# mosquino.net
KiCad netlist of a schematic drawn in EAGLE
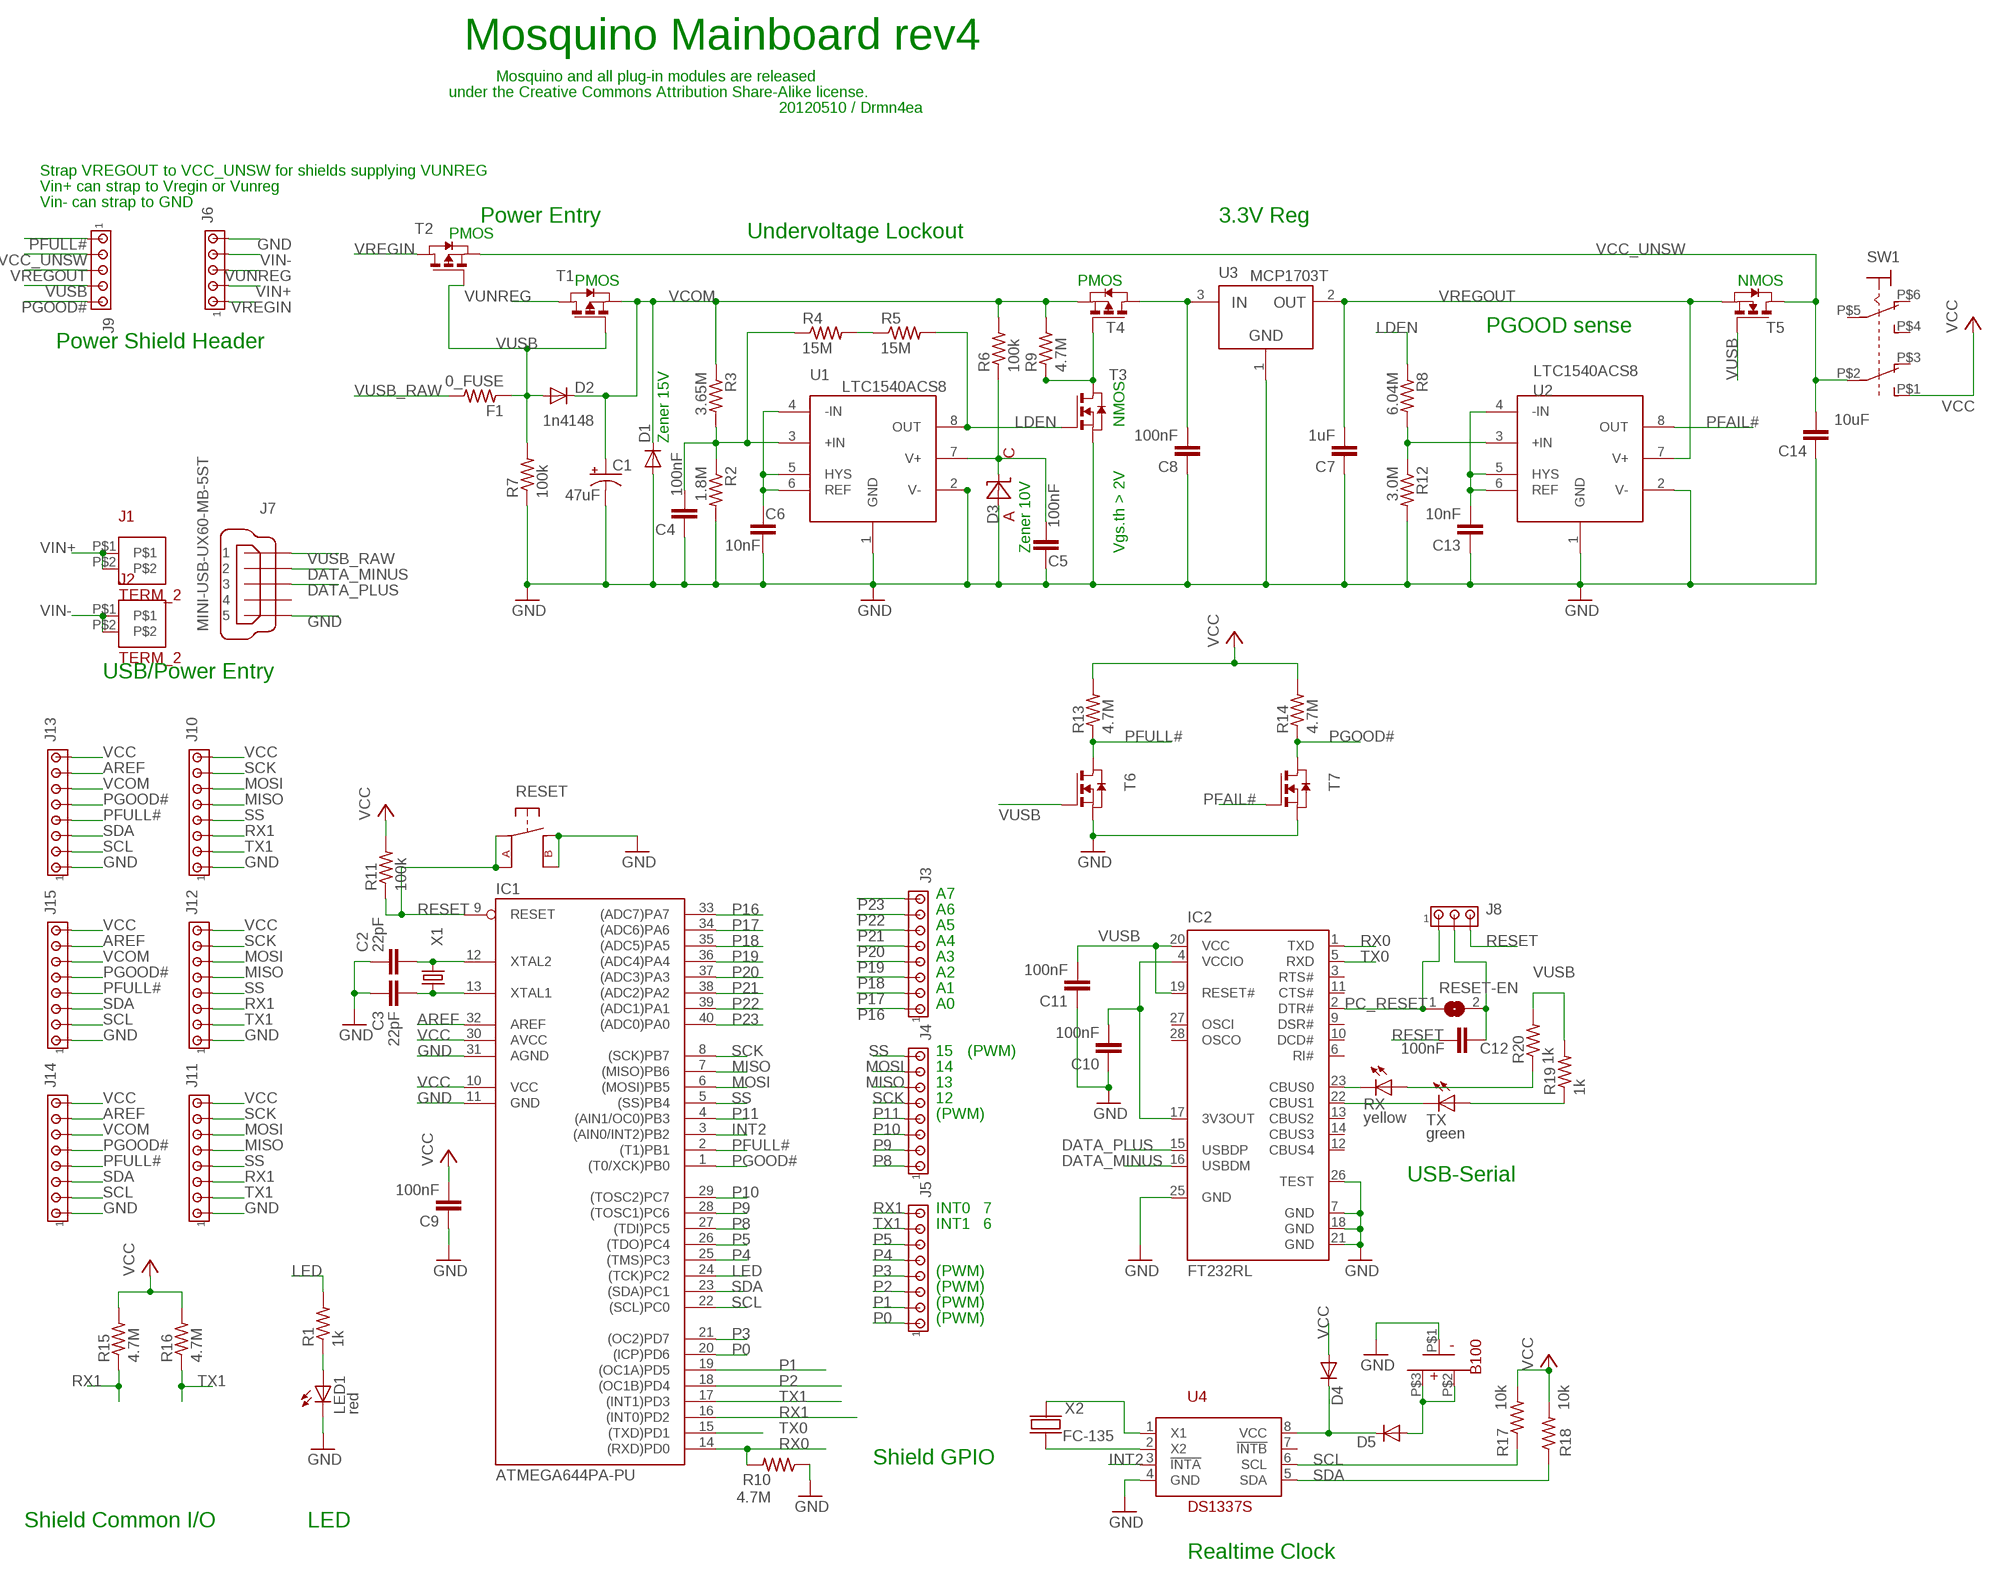
[diagram p0: schematic, sheet 1]

(export (version "E")
  (design (tool "Eeschema 10.0.6"))
  (components
    (comp (ref "B100")
      (value "BK885_CR1225_COIN_BATTERY_HOLDER_SMD")
      (footprint "eagle-import:BK885_CR1225_COIN_BATTERY_HOLDER_SMD")
      (libsource (lib "eagle-import") (part "BK885_CR1225_COIN_BATTERY_HOLDER_SMD"))
    )
    (comp (ref "C1")
      (value "47uF")
      (footprint "eagle-import:PANASONIC_D")
      (libsource (lib "eagle-import") (part "CPOL-USD"))
    )
    (comp (ref "C2")
      (value "22pF")
      (footprint "eagle-import:C0805K")
      (libsource (lib "eagle-import") (part "C-EUC0805K"))
    )
    (comp (ref "C3")
      (value "22pF")
      (footprint "eagle-import:C0805K")
      (libsource (lib "eagle-import") (part "C-EUC0805K"))
    )
    (comp (ref "C4")
      (value "100nF")
      (footprint "eagle-import:C0805")
      (libsource (lib "eagle-import") (part "C-EUC0805"))
    )
    (comp (ref "C5")
      (value "100nF")
      (footprint "eagle-import:C0805")
      (libsource (lib "eagle-import") (part "C-EUC0805"))
    )
    (comp (ref "C6")
      (value "10nF")
      (footprint "eagle-import:C0805")
      (libsource (lib "eagle-import") (part "C-EUC0805"))
    )
    (comp (ref "C7")
      (value "1uF")
      (footprint "eagle-import:C0805")
      (libsource (lib "eagle-import") (part "C-EUC0805"))
    )
    (comp (ref "C8")
      (value "100nF")
      (footprint "eagle-import:C0805")
      (libsource (lib "eagle-import") (part "C-EUC0805"))
    )
    (comp (ref "C9")
      (value "100nF")
      (footprint "eagle-import:C0805K")
      (libsource (lib "eagle-import") (part "C-EUC0805K"))
    )
    (comp (ref "C10")
      (value "100nF")
      (footprint "eagle-import:C0805K")
      (libsource (lib "eagle-import") (part "C-EUC0805K"))
    )
    (comp (ref "C11")
      (value "100nF")
      (footprint "eagle-import:C0805K")
      (libsource (lib "eagle-import") (part "C-EUC0805K"))
    )
    (comp (ref "C12")
      (value "100nF")
      (footprint "eagle-import:C0805K")
      (libsource (lib "eagle-import") (part "C-EUC0805K"))
    )
    (comp (ref "C13")
      (value "10nF")
      (footprint "eagle-import:C0805")
      (libsource (lib "eagle-import") (part "C-EUC0805"))
    )
    (comp (ref "C14")
      (value "10uF")
      (footprint "eagle-import:C0805K")
      (libsource (lib "eagle-import") (part "C-EUC0805K"))
    )
    (comp (ref "D1")
      (value "BZT52C15-7-F")
      (footprint "eagle-import:SOD123")
      (libsource (lib "eagle-import") (part "DIODE-SOD123"))
    )
    (comp (ref "D2")
      (value "1n4148")
      (footprint "eagle-import:SOD123")
      (libsource (lib "eagle-import") (part "DIODE-SOD123"))
    )
    (comp (ref "D3")
      (value "BZT52C10-7-F")
      (footprint "eagle-import:SOD123")
      (libsource (lib "eagle-import") (part "DIODE_ZENER_CZRM27C200P-G"))
    )
    (comp (ref "D4")
      (value "MMSD301T1G")
      (footprint "eagle-import:SOD123")
      (libsource (lib "eagle-import") (part "DIODE-SOD123"))
    )
    (comp (ref "D5")
      (value "MMSD301T1G")
      (footprint "eagle-import:SOD123")
      (libsource (lib "eagle-import") (part "DIODE-SOD123"))
    )
    (comp (ref "F1")
      (value "0_FUSE")
      (footprint "eagle-import:R0805")
      (libsource (lib "eagle-import") (part "R-US_R0805"))
    )
    (comp (ref "IC1")
      (value "ATMEGA644PA-PU")
      (footprint "eagle-import:DIL40")
      (libsource (lib "eagle-import") (part "MEGA323-P"))
    )
    (comp (ref "IC2")
      (value "FT232RL")
      (footprint "eagle-import:SSOP28")
      (libsource (lib "eagle-import") (part "FT232RL"))
    )
    (comp (ref "J1")
      (value "TERM_2")
      (footprint "eagle-import:TERM_3POINT5MM")
      (libsource (lib "eagle-import") (part "TERM_2"))
    )
    (comp (ref "J2")
      (value "TERM_2")
      (footprint "eagle-import:TERM_3POINT5MM")
      (libsource (lib "eagle-import") (part "TERM_2"))
    )
    (comp (ref "J3")
      (value "MTA08-100")
      (footprint "eagle-import:10X08MTA")
      (libsource (lib "eagle-import") (part "MTA08-100"))
    )
    (comp (ref "J4")
      (value "MTA08-100")
      (footprint "eagle-import:10X08MTA")
      (libsource (lib "eagle-import") (part "MTA08-100"))
    )
    (comp (ref "J5")
      (value "MTA08-100")
      (footprint "eagle-import:10X08MTA")
      (libsource (lib "eagle-import") (part "MTA08-100"))
    )
    (comp (ref "J6")
      (value "MTA05-100")
      (footprint "eagle-import:10X05MTA")
      (libsource (lib "eagle-import") (part "MTA05-100"))
    )
    (comp (ref "J7")
      (value "MINI-USB-UX60-MB-5ST")
      (footprint "eagle-import:UX60-MB-5ST")
      (libsource (lib "eagle-import") (part "MINI-USB-UX60-MB-5ST"))
    )
    (comp (ref "J8")
      (value "MTA03-100")
      (footprint "eagle-import:10X03MTA")
      (libsource (lib "eagle-import") (part "MTA03-100"))
    )
    (comp (ref "J9")
      (value "MTA05-100")
      (footprint "eagle-import:10X05MTA")
      (libsource (lib "eagle-import") (part "MTA05-100"))
    )
    (comp (ref "J10")
      (value "MTA08-100")
      (footprint "eagle-import:10X08MTA")
      (libsource (lib "eagle-import") (part "MTA08-100"))
    )
    (comp (ref "J11")
      (value "MTA08-100")
      (footprint "eagle-import:10X08MTA")
      (libsource (lib "eagle-import") (part "MTA08-100"))
    )
    (comp (ref "J12")
      (value "MTA08-100")
      (footprint "eagle-import:10X08MTA")
      (libsource (lib "eagle-import") (part "MTA08-100"))
    )
    (comp (ref "J13")
      (value "MTA08-100")
      (footprint "eagle-import:10X08MTA")
      (libsource (lib "eagle-import") (part "MTA08-100"))
    )
    (comp (ref "J14")
      (value "MTA08-100")
      (footprint "eagle-import:10X08MTA")
      (libsource (lib "eagle-import") (part "MTA08-100"))
    )
    (comp (ref "J15")
      (value "MTA08-100")
      (footprint "eagle-import:10X08MTA")
      (libsource (lib "eagle-import") (part "MTA08-100"))
    )
    (comp (ref "LED1")
      (value "red")
      (footprint "eagle-import:CHIP-LED0805")
      (libsource (lib "eagle-import") (part "LEDCHIP-LED0805"))
    )
    (comp (ref "R1")
      (value "1k")
      (footprint "eagle-import:R0805")
      (libsource (lib "eagle-import") (part "R-US_R0805"))
    )
    (comp (ref "R2")
      (value "1.8M")
      (footprint "eagle-import:R0805")
      (libsource (lib "eagle-import") (part "R-US_R0805"))
    )
    (comp (ref "R3")
      (value "3.65M")
      (footprint "eagle-import:R0805")
      (libsource (lib "eagle-import") (part "R-US_R0805"))
    )
    (comp (ref "R4")
      (value "15M")
      (footprint "eagle-import:R0805")
      (libsource (lib "eagle-import") (part "R-US_R0805"))
    )
    (comp (ref "R5")
      (value "15M")
      (footprint "eagle-import:R0805")
      (libsource (lib "eagle-import") (part "R-US_R0805"))
    )
    (comp (ref "R6")
      (value "100k")
      (footprint "eagle-import:R0805")
      (libsource (lib "eagle-import") (part "R-US_R0805"))
    )
    (comp (ref "R7")
      (value "100k")
      (footprint "eagle-import:R0805")
      (libsource (lib "eagle-import") (part "R-US_R0805"))
    )
    (comp (ref "R8")
      (value "6.04M")
      (footprint "eagle-import:R0805")
      (libsource (lib "eagle-import") (part "R-US_R0805"))
    )
    (comp (ref "R9")
      (value "4.7M")
      (footprint "eagle-import:R0805")
      (libsource (lib "eagle-import") (part "R-US_R0805"))
    )
    (comp (ref "R10")
      (value "4.7M")
      (footprint "eagle-import:R0805")
      (libsource (lib "eagle-import") (part "R-US_R0805"))
    )
    (comp (ref "R11")
      (value "100k")
      (footprint "eagle-import:R0805")
      (libsource (lib "eagle-import") (part "R-US_R0805"))
    )
    (comp (ref "R12")
      (value "3.0M")
      (footprint "eagle-import:R0805")
      (libsource (lib "eagle-import") (part "R-US_R0805"))
    )
    (comp (ref "R13")
      (value "4.7M")
      (footprint "eagle-import:R0805")
      (libsource (lib "eagle-import") (part "R-US_R0805"))
    )
    (comp (ref "R14")
      (value "4.7M")
      (footprint "eagle-import:R0805")
      (libsource (lib "eagle-import") (part "R-US_R0805"))
    )
    (comp (ref "R15")
      (value "4.7M")
      (footprint "eagle-import:R0805")
      (libsource (lib "eagle-import") (part "R-US_R0805"))
    )
    (comp (ref "R16")
      (value "4.7M")
      (footprint "eagle-import:R0805")
      (libsource (lib "eagle-import") (part "R-US_R0805"))
    )
    (comp (ref "R17")
      (value "10k")
      (footprint "eagle-import:R0805")
      (libsource (lib "eagle-import") (part "R-US_R0805"))
    )
    (comp (ref "R18")
      (value "10k")
      (footprint "eagle-import:R0805")
      (libsource (lib "eagle-import") (part "R-US_R0805"))
    )
    (comp (ref "R19")
      (value "1k")
      (footprint "eagle-import:R0805")
      (libsource (lib "eagle-import") (part "R-US_R0805"))
    )
    (comp (ref "R20")
      (value "1k")
      (footprint "eagle-import:R0805")
      (libsource (lib "eagle-import") (part "R-US_R0805"))
    )
    (comp (ref "RESET")
      (value "EVQ_TACT_SW_6X6POINT5")
      (footprint "eagle-import:EVQ_TACT_SW_6X6POINT5")
      (libsource (lib "eagle-import") (part "EVQ_TACT_SW_6X6POINT5"))
    )
    (comp (ref "RESET-EN")
      (value "SJ")
      (footprint "eagle-import:SJ")
      (libsource (lib "eagle-import") (part "SJ"))
    )
    (comp (ref "RX")
      (value "yellow")
      (footprint "eagle-import:CHIP-LED0805")
      (libsource (lib "eagle-import") (part "LEDCHIP-LED0805"))
    )
    (comp (ref "SW1")
      (value "SW_DPDT_EG1390")
      (footprint "eagle-import:EG1390_SWITCH_DPDT")
      (libsource (lib "eagle-import") (part "SW_DPDT_EG1390"))
    )
    (comp (ref "T1")
      (value "DMP3098L-7")
      (footprint "eagle-import:SOT-23")
      (libsource (lib "eagle-import") (part "PMOSSOT23"))
    )
    (comp (ref "T2")
      (value "DMP3098L-7")
      (footprint "eagle-import:SOT-23")
      (libsource (lib "eagle-import") (part "PMOSSOT23"))
    )
    (comp (ref "T3")
      (value "IRFML8244TRPBF")
      (footprint "eagle-import:SOT-23")
      (libsource (lib "eagle-import") (part "NMOSSOT23"))
    )
    (comp (ref "T4")
      (value "DMP3098L-7")
      (footprint "eagle-import:SOT-23")
      (libsource (lib "eagle-import") (part "PMOSSOT23"))
    )
    (comp (ref "T5")
      (value "BSH103")
      (footprint "eagle-import:SOT-23")
      (libsource (lib "eagle-import") (part "NMOSSOT23"))
    )
    (comp (ref "T6")
      (value "IRFML8244TRPBF")
      (footprint "eagle-import:SOT-23")
      (libsource (lib "eagle-import") (part "NMOSSOT23"))
    )
    (comp (ref "T7")
      (value "IRFML8244TRPBF")
      (footprint "eagle-import:SOT-23")
      (libsource (lib "eagle-import") (part "NMOSSOT23"))
    )
    (comp (ref "TX")
      (value "green")
      (footprint "eagle-import:CHIP-LED0805")
      (libsource (lib "eagle-import") (part "LEDCHIP-LED0805"))
    )
    (comp (ref "U1")
      (value "LTC1540ACS8")
      (footprint "eagle-import:SO-8")
      (libsource (lib "eagle-import") (part "LTC1540ACS8"))
    )
    (comp (ref "U2")
      (value "LTC1540ACS8")
      (footprint "eagle-import:SO-8")
      (libsource (lib "eagle-import") (part "LTC1540ACS8"))
    )
    (comp (ref "U3")
      (value "MCP1703T")
      (footprint "eagle-import:SOT23")
      (libsource (lib "eagle-import") (part "MCP1700T"))
    )
    (comp (ref "U4")
      (value "DS1337S")
      (footprint "eagle-import:SO-8")
      (libsource (lib "eagle-import") (part "DS1337S"))
    )
    (comp (ref "X1")
      (value "ABLS-4.000MHZ-B4-T")
      (footprint "eagle-import:SM49")
      (libsource (lib "eagle-import") (part "CRYSTALSM49"))
    )
    (comp (ref "X2")
      (value "FC-135")
      (footprint "eagle-import:FC-135")
      (libsource (lib "eagle-import") (part "FC-135"))
    )
  )
  (nets
    (net (code "1") (name "/AREF") (class "Default")
      (node (ref "IC1") (pin "32") (pinfunction "AREF_32") (pintype "power_in"))
      (node (ref "J13") (pin "7") (pinfunction "7_7") (pintype "passive"))
      (node (ref "J14") (pin "7") (pinfunction "7_7") (pintype "passive"))
      (node (ref "J15") (pin "7") (pinfunction "7_7") (pintype "passive"))
    )
    (net (code "2") (name "/DATA_MINUS") (class "Default")
      (node (ref "IC2") (pin "16") (pinfunction "USBDM_16") (pintype "input"))
      (node (ref "J7") (pin "2") (pinfunction "2_2") (pintype "input"))
    )
    (net (code "3") (name "/DATA_PLUS") (class "Default")
      (node (ref "IC2") (pin "15") (pinfunction "USBDP_15") (pintype "input"))
      (node (ref "J7") (pin "3") (pinfunction "3_3") (pintype "input"))
    )
    (net (code "4") (name "/INT2") (class "Default")
      (node (ref "IC1") (pin "3") (pinfunction "(AIN0/INT2)PB2_3") (pintype "bidirectional"))
      (node (ref "U4") (pin "3") (pinfunction "~{INTA}_3") (pintype "bidirectional"))
    )
    (net (code "5") (name "/LDEN") (class "Default")
      (node (ref "R5") (pin "2") (pinfunction "2_2") (pintype "passive"))
      (node (ref "R8") (pin "1") (pinfunction "1_1") (pintype "passive"))
      (node (ref "T3") (pin "3") (pinfunction "G_3") (pintype "passive"))
      (node (ref "U1") (pin "8") (pinfunction "OUT_8") (pintype "bidirectional"))
    )
    (net (code "6") (name "/LED") (class "Default")
      (node (ref "IC1") (pin "24") (pinfunction "(TCK)PC2_24") (pintype "bidirectional"))
      (node (ref "R1") (pin "2") (pinfunction "2_2") (pintype "passive"))
    )
    (net (code "7") (name "/MISO") (class "Default")
      (node (ref "IC1") (pin "7") (pinfunction "(MISO)PB6_7") (pintype "bidirectional"))
      (node (ref "J10") (pin "5") (pinfunction "5_5") (pintype "passive"))
      (node (ref "J11") (pin "5") (pinfunction "5_5") (pintype "passive"))
      (node (ref "J12") (pin "5") (pinfunction "5_5") (pintype "passive"))
      (node (ref "J4") (pin "6") (pinfunction "6_6") (pintype "passive"))
    )
    (net (code "8") (name "/MOSI") (class "Default")
      (node (ref "IC1") (pin "6") (pinfunction "(MOSI)PB5_6") (pintype "bidirectional"))
      (node (ref "J10") (pin "6") (pinfunction "6_6") (pintype "passive"))
      (node (ref "J11") (pin "6") (pinfunction "6_6") (pintype "passive"))
      (node (ref "J12") (pin "6") (pinfunction "6_6") (pintype "passive"))
      (node (ref "J4") (pin "7") (pinfunction "7_7") (pintype "passive"))
    )
    (net (code "9") (name "/P0") (class "Default")
      (node (ref "IC1") (pin "20") (pinfunction "(ICP)PD6_20") (pintype "bidirectional"))
      (node (ref "J5") (pin "1") (pinfunction "1_1") (pintype "passive"))
    )
    (net (code "10") (name "/P1") (class "Default")
      (node (ref "IC1") (pin "19") (pinfunction "(OC1A)PD5_19") (pintype "bidirectional"))
      (node (ref "J5") (pin "2") (pinfunction "2_2") (pintype "passive"))
    )
    (net (code "11") (name "/P2") (class "Default")
      (node (ref "IC1") (pin "18") (pinfunction "(OC1B)PD4_18") (pintype "bidirectional"))
      (node (ref "J5") (pin "3") (pinfunction "3_3") (pintype "passive"))
    )
    (net (code "12") (name "/P3") (class "Default")
      (node (ref "IC1") (pin "21") (pinfunction "(OC2)PD7_21") (pintype "bidirectional"))
      (node (ref "J5") (pin "4") (pinfunction "4_4") (pintype "passive"))
    )
    (net (code "13") (name "/P4") (class "Default")
      (node (ref "IC1") (pin "25") (pinfunction "(TMS)PC3_25") (pintype "bidirectional"))
      (node (ref "J5") (pin "5") (pinfunction "5_5") (pintype "passive"))
    )
    (net (code "14") (name "/P5") (class "Default")
      (node (ref "IC1") (pin "26") (pinfunction "(TDO)PC4_26") (pintype "bidirectional"))
      (node (ref "J5") (pin "6") (pinfunction "6_6") (pintype "passive"))
    )
    (net (code "15") (name "/P8") (class "Default")
      (node (ref "IC1") (pin "27") (pinfunction "(TDI)PC5_27") (pintype "bidirectional"))
      (node (ref "J4") (pin "1") (pinfunction "1_1") (pintype "passive"))
    )
    (net (code "16") (name "/P9") (class "Default")
      (node (ref "IC1") (pin "28") (pinfunction "(TOSC1)PC6_28") (pintype "bidirectional"))
      (node (ref "J4") (pin "2") (pinfunction "2_2") (pintype "passive"))
    )
    (net (code "17") (name "/P10") (class "Default")
      (node (ref "IC1") (pin "29") (pinfunction "(TOSC2)PC7_29") (pintype "bidirectional"))
      (node (ref "J4") (pin "3") (pinfunction "3_3") (pintype "passive"))
    )
    (net (code "18") (name "/P11") (class "Default")
      (node (ref "IC1") (pin "4") (pinfunction "(AIN1/OC0)PB3_4") (pintype "bidirectional"))
      (node (ref "J4") (pin "4") (pinfunction "4_4") (pintype "passive"))
    )
    (net (code "19") (name "/P16") (class "Default")
      (node (ref "IC1") (pin "33") (pinfunction "(ADC7)PA7_33") (pintype "bidirectional"))
      (node (ref "J3") (pin "1") (pinfunction "1_1") (pintype "passive"))
    )
    (net (code "20") (name "/P17") (class "Default")
      (node (ref "IC1") (pin "34") (pinfunction "(ADC6)PA6_34") (pintype "bidirectional"))
      (node (ref "J3") (pin "2") (pinfunction "2_2") (pintype "passive"))
    )
    (net (code "21") (name "/P18") (class "Default")
      (node (ref "IC1") (pin "35") (pinfunction "(ADC5)PA5_35") (pintype "bidirectional"))
      (node (ref "J3") (pin "3") (pinfunction "3_3") (pintype "passive"))
    )
    (net (code "22") (name "/P19") (class "Default")
      (node (ref "IC1") (pin "36") (pinfunction "(ADC4)PA4_36") (pintype "bidirectional"))
      (node (ref "J3") (pin "4") (pinfunction "4_4") (pintype "passive"))
    )
    (net (code "23") (name "/P20") (class "Default")
      (node (ref "IC1") (pin "37") (pinfunction "(ADC3)PA3_37") (pintype "bidirectional"))
      (node (ref "J3") (pin "5") (pinfunction "5_5") (pintype "passive"))
    )
    (net (code "24") (name "/P21") (class "Default")
      (node (ref "IC1") (pin "38") (pinfunction "(ADC2)PA2_38") (pintype "bidirectional"))
      (node (ref "J3") (pin "6") (pinfunction "6_6") (pintype "passive"))
    )
    (net (code "25") (name "/P22") (class "Default")
      (node (ref "IC1") (pin "39") (pinfunction "(ADC1)PA1_39") (pintype "bidirectional"))
      (node (ref "J3") (pin "7") (pinfunction "7_7") (pintype "passive"))
    )
    (net (code "26") (name "/P23") (class "Default")
      (node (ref "IC1") (pin "40") (pinfunction "(ADC0)PA0_40") (pintype "bidirectional"))
      (node (ref "J3") (pin "8") (pinfunction "8_8") (pintype "passive"))
    )
    (net (code "27") (name "/PC_RESET") (class "Default")
      (node (ref "IC2") (pin "2") (pinfunction "DTR#_2") (pintype "input"))
      (node (ref "J8") (pin "1") (pinfunction "1_1") (pintype "passive"))
      (node (ref "RESET-EN") (pin "1") (pinfunction "1_1") (pintype "passive"))
    )
    (net (code "28") (name "/PFAIL#") (class "Default")
      (node (ref "T7") (pin "3") (pinfunction "G_3") (pintype "passive"))
      (node (ref "U2") (pin "8") (pinfunction "OUT_8") (pintype "bidirectional"))
    )
    (net (code "29") (name "/PFULL#") (class "Default")
      (node (ref "IC1") (pin "2") (pinfunction "(T1)PB1_2") (pintype "bidirectional"))
      (node (ref "J13") (pin "4") (pinfunction "4_4") (pintype "passive"))
      (node (ref "J14") (pin "4") (pinfunction "4_4") (pintype "passive"))
      (node (ref "J15") (pin "4") (pinfunction "4_4") (pintype "passive"))
      (node (ref "J9") (pin "1") (pinfunction "1_1") (pintype "passive"))
      (node (ref "R13") (pin "1") (pinfunction "1_1") (pintype "passive"))
      (node (ref "T6") (pin "1") (pinfunction "D_1") (pintype "passive"))
    )
    (net (code "30") (name "/PGOOD#") (class "Default")
      (node (ref "IC1") (pin "1") (pinfunction "(T0/XCK)PB0_1") (pintype "bidirectional"))
      (node (ref "J13") (pin "5") (pinfunction "5_5") (pintype "passive"))
      (node (ref "J14") (pin "5") (pinfunction "5_5") (pintype "passive"))
      (node (ref "J15") (pin "5") (pinfunction "5_5") (pintype "passive"))
      (node (ref "J9") (pin "5") (pinfunction "5_5") (pintype "passive"))
      (node (ref "R14") (pin "1") (pinfunction "1_1") (pintype "passive"))
      (node (ref "T7") (pin "1") (pinfunction "D_1") (pintype "passive"))
    )
    (net (code "31") (name "/RESET") (class "Default")
      (node (ref "C12") (pin "2") (pinfunction "2_2") (pintype "passive"))
      (node (ref "IC1") (pin "9") (pinfunction "RESET_9") (pintype "input"))
      (node (ref "J8") (pin "3") (pinfunction "3_3") (pintype "passive"))
      (node (ref "R11") (pin "1") (pinfunction "1_1") (pintype "passive"))
      (node (ref "RESET") (pin "A") (pinfunction "A_A") (pintype "passive"))
      (node (ref "RESET") (pin "A2") (pinfunction "A1_A2") (pintype "bidirectional"))
    )
    (net (code "32") (name "/RX0") (class "Default")
      (node (ref "IC1") (pin "14") (pinfunction "(RXD)PD0_14") (pintype "bidirectional"))
      (node (ref "IC2") (pin "1") (pinfunction "TXD_1") (pintype "input"))
      (node (ref "R10") (pin "2") (pinfunction "2_2") (pintype "passive"))
    )
    (net (code "33") (name "/RX1") (class "Default")
      (node (ref "IC1") (pin "16") (pinfunction "(INT0)PD2_16") (pintype "bidirectional"))
      (node (ref "J10") (pin "3") (pinfunction "3_3") (pintype "passive"))
      (node (ref "J11") (pin "3") (pinfunction "3_3") (pintype "passive"))
      (node (ref "J12") (pin "3") (pinfunction "3_3") (pintype "passive"))
      (node (ref "J5") (pin "8") (pinfunction "8_8") (pintype "passive"))
      (node (ref "R15") (pin "1") (pinfunction "1_1") (pintype "passive"))
    )
    (net (code "34") (name "/SCK") (class "Default")
      (node (ref "IC1") (pin "8") (pinfunction "(SCK)PB7_8") (pintype "bidirectional"))
      (node (ref "J10") (pin "7") (pinfunction "7_7") (pintype "passive"))
      (node (ref "J11") (pin "7") (pinfunction "7_7") (pintype "passive"))
      (node (ref "J12") (pin "7") (pinfunction "7_7") (pintype "passive"))
      (node (ref "J4") (pin "5") (pinfunction "5_5") (pintype "passive"))
    )
    (net (code "35") (name "/SCL") (class "Default")
      (node (ref "IC1") (pin "22") (pinfunction "(SCL)PC0_22") (pintype "bidirectional"))
      (node (ref "J13") (pin "2") (pinfunction "2_2") (pintype "passive"))
      (node (ref "J14") (pin "2") (pinfunction "2_2") (pintype "passive"))
      (node (ref "J15") (pin "2") (pinfunction "2_2") (pintype "passive"))
      (node (ref "R17") (pin "1") (pinfunction "1_1") (pintype "passive"))
      (node (ref "U4") (pin "6") (pinfunction "SCL_6") (pintype "bidirectional"))
    )
    (net (code "36") (name "/SDA") (class "Default")
      (node (ref "IC1") (pin "23") (pinfunction "(SDA)PC1_23") (pintype "bidirectional"))
      (node (ref "J13") (pin "3") (pinfunction "3_3") (pintype "passive"))
      (node (ref "J14") (pin "3") (pinfunction "3_3") (pintype "passive"))
      (node (ref "J15") (pin "3") (pinfunction "3_3") (pintype "passive"))
      (node (ref "R18") (pin "1") (pinfunction "1_1") (pintype "passive"))
      (node (ref "U4") (pin "5") (pinfunction "SDA_5") (pintype "bidirectional"))
    )
    (net (code "37") (name "/SS") (class "Default")
      (node (ref "IC1") (pin "5") (pinfunction "(SS)PB4_5") (pintype "bidirectional"))
      (node (ref "J10") (pin "4") (pinfunction "4_4") (pintype "passive"))
      (node (ref "J11") (pin "4") (pinfunction "4_4") (pintype "passive"))
      (node (ref "J12") (pin "4") (pinfunction "4_4") (pintype "passive"))
      (node (ref "J4") (pin "8") (pinfunction "8_8") (pintype "passive"))
    )
    (net (code "38") (name "/TX0") (class "Default")
      (node (ref "IC1") (pin "15") (pinfunction "(TXD)PD1_15") (pintype "bidirectional"))
      (node (ref "IC2") (pin "5") (pinfunction "RXD_5") (pintype "input"))
    )
    (net (code "39") (name "/TX1") (class "Default")
      (node (ref "IC1") (pin "17") (pinfunction "(INT1)PD3_17") (pintype "bidirectional"))
      (node (ref "J10") (pin "2") (pinfunction "2_2") (pintype "passive"))
      (node (ref "J11") (pin "2") (pinfunction "2_2") (pintype "passive"))
      (node (ref "J12") (pin "2") (pinfunction "2_2") (pintype "passive"))
      (node (ref "J5") (pin "7") (pinfunction "7_7") (pintype "passive"))
      (node (ref "R16") (pin "1") (pinfunction "1_1") (pintype "passive"))
    )
    (net (code "40") (name "/VCC_UNSW") (class "Default")
      (node (ref "C14") (pin "2") (pinfunction "2_2") (pintype "passive"))
      (node (ref "J9") (pin "2") (pinfunction "2_2") (pintype "passive"))
      (node (ref "SW1") (pin "P$2") (pinfunction "COM1_P$2") (pintype "passive"))
      (node (ref "T2") (pin "2") (pinfunction "S_2") (pintype "passive"))
      (node (ref "T5") (pin "1") (pinfunction "D_1") (pintype "passive"))
    )
    (net (code "41") (name "/VCOM") (class "Default")
      (node (ref "C1") (pin "+") (pinfunction "+_+") (pintype "passive"))
      (node (ref "D1") (pin "C") (pinfunction "C_C") (pintype "passive"))
      (node (ref "D2") (pin "C") (pinfunction "C_C") (pintype "passive"))
      (node (ref "J13") (pin "6") (pinfunction "6_6") (pintype "passive"))
      (node (ref "J14") (pin "6") (pinfunction "6_6") (pintype "passive"))
      (node (ref "J15") (pin "6") (pinfunction "6_6") (pintype "passive"))
      (node (ref "R3") (pin "1") (pinfunction "1_1") (pintype "passive"))
      (node (ref "R6") (pin "2") (pinfunction "2_2") (pintype "passive"))
      (node (ref "R9") (pin "2") (pinfunction "2_2") (pintype "passive"))
      (node (ref "T1") (pin "2") (pinfunction "S_2") (pintype "passive"))
      (node (ref "T4") (pin "2") (pinfunction "S_2") (pintype "passive"))
    )
    (net (code "42") (name "/VIN+") (class "Default")
      (node (ref "J1") (pin "P$1") (pinfunction "P$1_P$1") (pintype "passive"))
      (node (ref "J1") (pin "P$2") (pinfunction "P$2_P$2") (pintype "passive"))
      (node (ref "J6") (pin "2") (pinfunction "2_2") (pintype "passive"))
    )
    (net (code "43") (name "/VIN-") (class "Default")
      (node (ref "J2") (pin "P$1") (pinfunction "P$1_P$1") (pintype "passive"))
      (node (ref "J2") (pin "P$2") (pinfunction "P$2_P$2") (pintype "passive"))
      (node (ref "J6") (pin "4") (pinfunction "4_4") (pintype "passive"))
    )
    (net (code "44") (name "/VREGIN") (class "Default")
      (node (ref "J6") (pin "1") (pinfunction "1_1") (pintype "passive"))
      (node (ref "T2") (pin "1") (pinfunction "D_1") (pintype "passive"))
    )
    (net (code "45") (name "/VREGOUT") (class "Default")
      (node (ref "C7") (pin "2") (pinfunction "2_2") (pintype "passive"))
      (node (ref "J9") (pin "3") (pinfunction "3_3") (pintype "passive"))
      (node (ref "T5") (pin "2") (pinfunction "S_2") (pintype "passive"))
      (node (ref "U2") (pin "7") (pinfunction "V+_7") (pintype "bidirectional"))
      (node (ref "U3") (pin "2") (pinfunction "OUT_2") (pintype "power_in"))
    )
    (net (code "46") (name "/VUNREG") (class "Default")
      (node (ref "J6") (pin "3") (pinfunction "3_3") (pintype "passive"))
      (node (ref "T1") (pin "1") (pinfunction "D_1") (pintype "passive"))
    )
    (net (code "47") (name "/VUSB") (class "Default")
      (node (ref "C11") (pin "2") (pinfunction "2_2") (pintype "passive"))
      (node (ref "D2") (pin "A") (pinfunction "A_A") (pintype "passive"))
      (node (ref "F1") (pin "1") (pinfunction "1_1") (pintype "passive"))
      (node (ref "IC2") (pin "19") (pinfunction "RESET#_19") (pintype "input"))
      (node (ref "IC2") (pin "20") (pinfunction "VCC_20") (pintype "input"))
      (node (ref "J9") (pin "4") (pinfunction "4_4") (pintype "passive"))
      (node (ref "R19") (pin "2") (pinfunction "2_2") (pintype "passive"))
      (node (ref "R20") (pin "2") (pinfunction "2_2") (pintype "passive"))
      (node (ref "R7") (pin "2") (pinfunction "2_2") (pintype "passive"))
      (node (ref "T1") (pin "3") (pinfunction "G_3") (pintype "passive"))
      (node (ref "T2") (pin "3") (pinfunction "G_3") (pintype "passive"))
      (node (ref "T5") (pin "3") (pinfunction "G_3") (pintype "passive"))
      (node (ref "T6") (pin "3") (pinfunction "G_3") (pintype "passive"))
    )
    (net (code "48") (name "/VUSB_RAW") (class "Default")
      (node (ref "F1") (pin "2") (pinfunction "2_2") (pintype "passive"))
      (node (ref "J7") (pin "1") (pinfunction "1_1") (pintype "input"))
    )
    (net (code "49") (name "GND") (class "Default")
      (node (ref "B100") (pin "P$1") (pinfunction "-_P$1") (pintype "power_in"))
      (node (ref "C1") (pin "-") (pinfunction "-_-") (pintype "passive"))
      (node (ref "C10") (pin "1") (pinfunction "1_1") (pintype "passive"))
      (node (ref "C11") (pin "1") (pinfunction "1_1") (pintype "passive"))
      (node (ref "C13") (pin "1") (pinfunction "1_1") (pintype "passive"))
      (node (ref "C14") (pin "1") (pinfunction "1_1") (pintype "passive"))
      (node (ref "C2") (pin "2") (pinfunction "2_2") (pintype "passive"))
      (node (ref "C3") (pin "1") (pinfunction "1_1") (pintype "passive"))
      (node (ref "C4") (pin "1") (pinfunction "1_1") (pintype "passive"))
      (node (ref "C5") (pin "1") (pinfunction "1_1") (pintype "passive"))
      (node (ref "C6") (pin "1") (pinfunction "1_1") (pintype "passive"))
      (node (ref "C7") (pin "1") (pinfunction "1_1") (pintype "passive"))
      (node (ref "C8") (pin "1") (pinfunction "1_1") (pintype "passive"))
      (node (ref "C9") (pin "1") (pinfunction "1_1") (pintype "passive"))
      (node (ref "D1") (pin "A") (pinfunction "A_A") (pintype "passive"))
      (node (ref "D3") (pin "A") (pinfunction "A_A") (pintype "passive"))
      (node (ref "IC1") (pin "11") (pinfunction "GND_11") (pintype "power_in"))
      (node (ref "IC1") (pin "31") (pinfunction "AGND_31") (pintype "power_in"))
      (node (ref "IC2") (pin "18") (pinfunction "GND_18") (pintype "input"))
      (node (ref "IC2") (pin "21") (pinfunction "GND_21") (pintype "input"))
      (node (ref "IC2") (pin "25") (pinfunction "GND_25") (pintype "input"))
      (node (ref "IC2") (pin "26") (pinfunction "TEST_26") (pintype "input"))
      (node (ref "IC2") (pin "7") (pinfunction "GND_7") (pintype "input"))
      (node (ref "J10") (pin "1") (pinfunction "1_1") (pintype "passive"))
      (node (ref "J11") (pin "1") (pinfunction "1_1") (pintype "passive"))
      (node (ref "J12") (pin "1") (pinfunction "1_1") (pintype "passive"))
      (node (ref "J13") (pin "1") (pinfunction "1_1") (pintype "passive"))
      (node (ref "J14") (pin "1") (pinfunction "1_1") (pintype "passive"))
      (node (ref "J15") (pin "1") (pinfunction "1_1") (pintype "passive"))
      (node (ref "J6") (pin "5") (pinfunction "5_5") (pintype "passive"))
      (node (ref "J7") (pin "5") (pinfunction "5_5") (pintype "input"))
      (node (ref "LED1") (pin "C") (pinfunction "C_C") (pintype "passive"))
      (node (ref "R10") (pin "1") (pinfunction "1_1") (pintype "passive"))
      (node (ref "R12") (pin "2") (pinfunction "2_2") (pintype "passive"))
      (node (ref "R2") (pin "2") (pinfunction "2_2") (pintype "passive"))
      (node (ref "R7") (pin "1") (pinfunction "1_1") (pintype "passive"))
      (node (ref "RESET") (pin "B") (pinfunction "B_B") (pintype "passive"))
      (node (ref "RESET") (pin "B2") (pinfunction "B1_B2") (pintype "bidirectional"))
      (node (ref "T3") (pin "2") (pinfunction "S_2") (pintype "passive"))
      (node (ref "T6") (pin "2") (pinfunction "S_2") (pintype "passive"))
      (node (ref "T7") (pin "2") (pinfunction "S_2") (pintype "passive"))
      (node (ref "U1") (pin "1") (pinfunction "GND_1") (pintype "bidirectional"))
      (node (ref "U1") (pin "2") (pinfunction "V-_2") (pintype "bidirectional"))
      (node (ref "U2") (pin "1") (pinfunction "GND_1") (pintype "bidirectional"))
      (node (ref "U2") (pin "2") (pinfunction "V-_2") (pintype "bidirectional"))
      (node (ref "U3") (pin "1") (pinfunction "GND_1") (pintype "power_in"))
      (node (ref "U4") (pin "4") (pinfunction "GND_4") (pintype "power_in"))
    )
    (net (code "50") (name "Net-(B100-+-PadP$2)") (class "Default")
      (node (ref "B100") (pin "P$2") (pinfunction "+_P$2") (pintype "power_in"))
      (node (ref "B100") (pin "P$3") (pinfunction "+_P$3") (pintype "power_in"))
      (node (ref "D5") (pin "A") (pinfunction "A_A") (pintype "passive"))
    )
    (net (code "51") (name "Net-(C12-Pad1)") (class "Default")
      (node (ref "C12") (pin "1") (pinfunction "1_1") (pintype "passive"))
      (node (ref "J8") (pin "2") (pinfunction "2_2") (pintype "passive"))
      (node (ref "RESET-EN") (pin "2") (pinfunction "2_2") (pintype "passive"))
    )
    (net (code "52") (name "Net-(IC1-XTAL1)") (class "Default")
      (node (ref "C3") (pin "2") (pinfunction "2_2") (pintype "passive"))
      (node (ref "IC1") (pin "13") (pinfunction "XTAL1_13") (pintype "bidirectional"))
      (node (ref "X1") (pin "1") (pinfunction "1_1") (pintype "passive"))
    )
    (net (code "53") (name "Net-(IC1-XTAL2)") (class "Default")
      (node (ref "C2") (pin "1") (pinfunction "1_1") (pintype "passive"))
      (node (ref "IC1") (pin "12") (pinfunction "XTAL2_12") (pintype "bidirectional"))
      (node (ref "X1") (pin "2") (pinfunction "2_2") (pintype "passive"))
    )
    (net (code "54") (name "Net-(IC2-3V3OUT)") (class "Default")
      (node (ref "C10") (pin "2") (pinfunction "2_2") (pintype "passive"))
      (node (ref "IC2") (pin "17") (pinfunction "3V3OUT_17") (pintype "input"))
      (node (ref "IC2") (pin "4") (pinfunction "VCCIO_4") (pintype "input"))
    )
    (net (code "55") (name "Net-(IC2-CBUS0)") (class "Default")
      (node (ref "IC2") (pin "23") (pinfunction "CBUS0_23") (pintype "input"))
      (node (ref "RX") (pin "C") (pinfunction "C_C") (pintype "passive"))
    )
    (net (code "56") (name "Net-(IC2-CBUS1)") (class "Default")
      (node (ref "IC2") (pin "22") (pinfunction "CBUS1_22") (pintype "input"))
      (node (ref "TX") (pin "C") (pinfunction "C_C") (pintype "passive"))
    )
    (net (code "57") (name "Net-(LED1-PadA)") (class "Default")
      (node (ref "LED1") (pin "A") (pinfunction "A_A") (pintype "passive"))
      (node (ref "R1") (pin "1") (pinfunction "1_1") (pintype "passive"))
    )
    (net (code "58") (name "Net-(R4-Pad2)") (class "Default")
      (node (ref "R4") (pin "2") (pinfunction "2_2") (pintype "passive"))
      (node (ref "R5") (pin "1") (pinfunction "1_1") (pintype "passive"))
    )
    (net (code "59") (name "Net-(R19-Pad1)") (class "Default")
      (node (ref "R19") (pin "1") (pinfunction "1_1") (pintype "passive"))
      (node (ref "TX") (pin "A") (pinfunction "A_A") (pintype "passive"))
    )
    (net (code "60") (name "Net-(R20-Pad1)") (class "Default")
      (node (ref "R20") (pin "1") (pinfunction "1_1") (pintype "passive"))
      (node (ref "RX") (pin "A") (pinfunction "A_A") (pintype "passive"))
    )
    (net (code "61") (name "Net-(T3-D)") (class "Default")
      (node (ref "R9") (pin "1") (pinfunction "1_1") (pintype "passive"))
      (node (ref "T3") (pin "1") (pinfunction "D_1") (pintype "passive"))
      (node (ref "T4") (pin "3") (pinfunction "G_3") (pintype "passive"))
    )
    (net (code "62") (name "Net-(T4-D)") (class "Default")
      (node (ref "C8") (pin "2") (pinfunction "2_2") (pintype "passive"))
      (node (ref "T4") (pin "1") (pinfunction "D_1") (pintype "passive"))
      (node (ref "U3") (pin "3") (pinfunction "IN_3") (pintype "power_in"))
    )
    (net (code "63") (name "Net-(U1-+IN)") (class "Default")
      (node (ref "C4") (pin "2") (pinfunction "2_2") (pintype "passive"))
      (node (ref "R2") (pin "1") (pinfunction "1_1") (pintype "passive"))
      (node (ref "R3") (pin "2") (pinfunction "2_2") (pintype "passive"))
      (node (ref "R4") (pin "1") (pinfunction "1_1") (pintype "passive"))
      (node (ref "U1") (pin "3") (pinfunction "+IN_3") (pintype "bidirectional"))
    )
    (net (code "64") (name "Net-(U1--IN)") (class "Default")
      (node (ref "C6") (pin "2") (pinfunction "2_2") (pintype "passive"))
      (node (ref "U1") (pin "4") (pinfunction "-IN_4") (pintype "bidirectional"))
      (node (ref "U1") (pin "5") (pinfunction "HYS_5") (pintype "bidirectional"))
      (node (ref "U1") (pin "6") (pinfunction "REF_6") (pintype "bidirectional"))
    )
    (net (code "65") (name "Net-(U1-V+)") (class "Default")
      (node (ref "C5") (pin "2") (pinfunction "2_2") (pintype "passive"))
      (node (ref "D3") (pin "C") (pinfunction "C_C") (pintype "passive"))
      (node (ref "R6") (pin "1") (pinfunction "1_1") (pintype "passive"))
      (node (ref "U1") (pin "7") (pinfunction "V+_7") (pintype "bidirectional"))
    )
    (net (code "66") (name "Net-(U2-+IN)") (class "Default")
      (node (ref "R12") (pin "1") (pinfunction "1_1") (pintype "passive"))
      (node (ref "R8") (pin "2") (pinfunction "2_2") (pintype "passive"))
      (node (ref "U2") (pin "3") (pinfunction "+IN_3") (pintype "bidirectional"))
    )
    (net (code "67") (name "Net-(U2--IN)") (class "Default")
      (node (ref "C13") (pin "2") (pinfunction "2_2") (pintype "passive"))
      (node (ref "U2") (pin "4") (pinfunction "-IN_4") (pintype "bidirectional"))
      (node (ref "U2") (pin "5") (pinfunction "HYS_5") (pintype "bidirectional"))
      (node (ref "U2") (pin "6") (pinfunction "REF_6") (pintype "bidirectional"))
    )
    (net (code "68") (name "Net-(U4-VCC)") (class "Default")
      (node (ref "D4") (pin "C") (pinfunction "C_C") (pintype "passive"))
      (node (ref "D5") (pin "C") (pinfunction "C_C") (pintype "passive"))
      (node (ref "U4") (pin "8") (pinfunction "VCC_8") (pintype "power_in"))
    )
    (net (code "69") (name "Net-(U4-X1)") (class "Default")
      (node (ref "U4") (pin "1") (pinfunction "X1_1") (pintype "bidirectional"))
      (node (ref "X2") (pin "P$1") (pinfunction "X1_P$1") (pintype "passive"))
    )
    (net (code "70") (name "Net-(U4-X2)") (class "Default")
      (node (ref "U4") (pin "2") (pinfunction "X2_2") (pintype "bidirectional"))
      (node (ref "X2") (pin "P$2") (pinfunction "X2_P$2") (pintype "passive"))
    )
    (net (code "71") (name "VCC") (class "Default")
      (node (ref "C9") (pin "2") (pinfunction "2_2") (pintype "passive"))
      (node (ref "D4") (pin "A") (pinfunction "A_A") (pintype "passive"))
      (node (ref "IC1") (pin "10") (pinfunction "VCC_10") (pintype "power_in"))
      (node (ref "IC1") (pin "30") (pinfunction "AVCC_30") (pintype "power_in"))
      (node (ref "J10") (pin "8") (pinfunction "8_8") (pintype "passive"))
      (node (ref "J11") (pin "8") (pinfunction "8_8") (pintype "passive"))
      (node (ref "J12") (pin "8") (pinfunction "8_8") (pintype "passive"))
      (node (ref "J13") (pin "8") (pinfunction "8_8") (pintype "passive"))
      (node (ref "J14") (pin "8") (pinfunction "8_8") (pintype "passive"))
      (node (ref "J15") (pin "8") (pinfunction "8_8") (pintype "passive"))
      (node (ref "R11") (pin "2") (pinfunction "2_2") (pintype "passive"))
      (node (ref "R13") (pin "2") (pinfunction "2_2") (pintype "passive"))
      (node (ref "R14") (pin "2") (pinfunction "2_2") (pintype "passive"))
      (node (ref "R15") (pin "2") (pinfunction "2_2") (pintype "passive"))
      (node (ref "R16") (pin "2") (pinfunction "2_2") (pintype "passive"))
      (node (ref "R17") (pin "2") (pinfunction "2_2") (pintype "passive"))
      (node (ref "R18") (pin "2") (pinfunction "2_2") (pintype "passive"))
      (node (ref "SW1") (pin "P$1") (pinfunction "ON1_P$1") (pintype "passive"))
    )
    (net (code "72") (name "unconnected-(IC2-CBUS2-Pad13)") (class "Default")
      (node (ref "IC2") (pin "13") (pinfunction "CBUS2_13") (pintype "input"))
    )
    (net (code "73") (name "unconnected-(IC2-CBUS3-Pad14)") (class "Default")
      (node (ref "IC2") (pin "14") (pinfunction "CBUS3_14") (pintype "input"))
    )
    (net (code "74") (name "unconnected-(IC2-CBUS4-Pad12)") (class "Default")
      (node (ref "IC2") (pin "12") (pinfunction "CBUS4_12") (pintype "input"))
    )
    (net (code "75") (name "unconnected-(IC2-CTS#-Pad11)") (class "Default")
      (node (ref "IC2") (pin "11") (pinfunction "CTS#_11") (pintype "input"))
    )
    (net (code "76") (name "unconnected-(IC2-DCD#-Pad10)") (class "Default")
      (node (ref "IC2") (pin "10") (pinfunction "DCD#_10") (pintype "input"))
    )
    (net (code "77") (name "unconnected-(IC2-DSR#-Pad9)") (class "Default")
      (node (ref "IC2") (pin "9") (pinfunction "DSR#_9") (pintype "input"))
    )
    (net (code "78") (name "unconnected-(IC2-OSCI-Pad27)") (class "Default")
      (node (ref "IC2") (pin "27") (pinfunction "OSCI_27") (pintype "input"))
    )
    (net (code "79") (name "unconnected-(IC2-OSCO-Pad28)") (class "Default")
      (node (ref "IC2") (pin "28") (pinfunction "OSCO_28") (pintype "input"))
    )
    (net (code "80") (name "unconnected-(IC2-RI#-Pad6)") (class "Default")
      (node (ref "IC2") (pin "6") (pinfunction "RI#_6") (pintype "input"))
    )
    (net (code "81") (name "unconnected-(IC2-RTS#-Pad3)") (class "Default")
      (node (ref "IC2") (pin "3") (pinfunction "RTS#_3") (pintype "input"))
    )
    (net (code "82") (name "unconnected-(J7-Pad4)") (class "Default")
      (node (ref "J7") (pin "4") (pinfunction "4_4") (pintype "input"))
    )
    (net (code "83") (name "unconnected-(SW1-COM2-PadP$5)") (class "Default")
      (node (ref "SW1") (pin "P$5") (pinfunction "COM2_P$5") (pintype "passive"))
    )
    (net (code "84") (name "unconnected-(SW1-OFF1-PadP$3)") (class "Default")
      (node (ref "SW1") (pin "P$3") (pinfunction "OFF1_P$3") (pintype "passive"))
    )
    (net (code "85") (name "unconnected-(SW1-OFF2-PadP$6)") (class "Default")
      (node (ref "SW1") (pin "P$6") (pinfunction "OFF2_P$6") (pintype "passive"))
    )
    (net (code "86") (name "unconnected-(SW1-ON2-PadP$4)") (class "Default")
      (node (ref "SW1") (pin "P$4") (pinfunction "ON2_P$4") (pintype "passive"))
    )
    (net (code "87") (name "unconnected-(U4-~{INTB}-Pad7)") (class "Default")
      (node (ref "U4") (pin "7") (pinfunction "~{INTB}_7") (pintype "bidirectional"))
    )
  )
)
